# circuito_rele.net
KiCad netlist of a schematic drawn in EAGLE
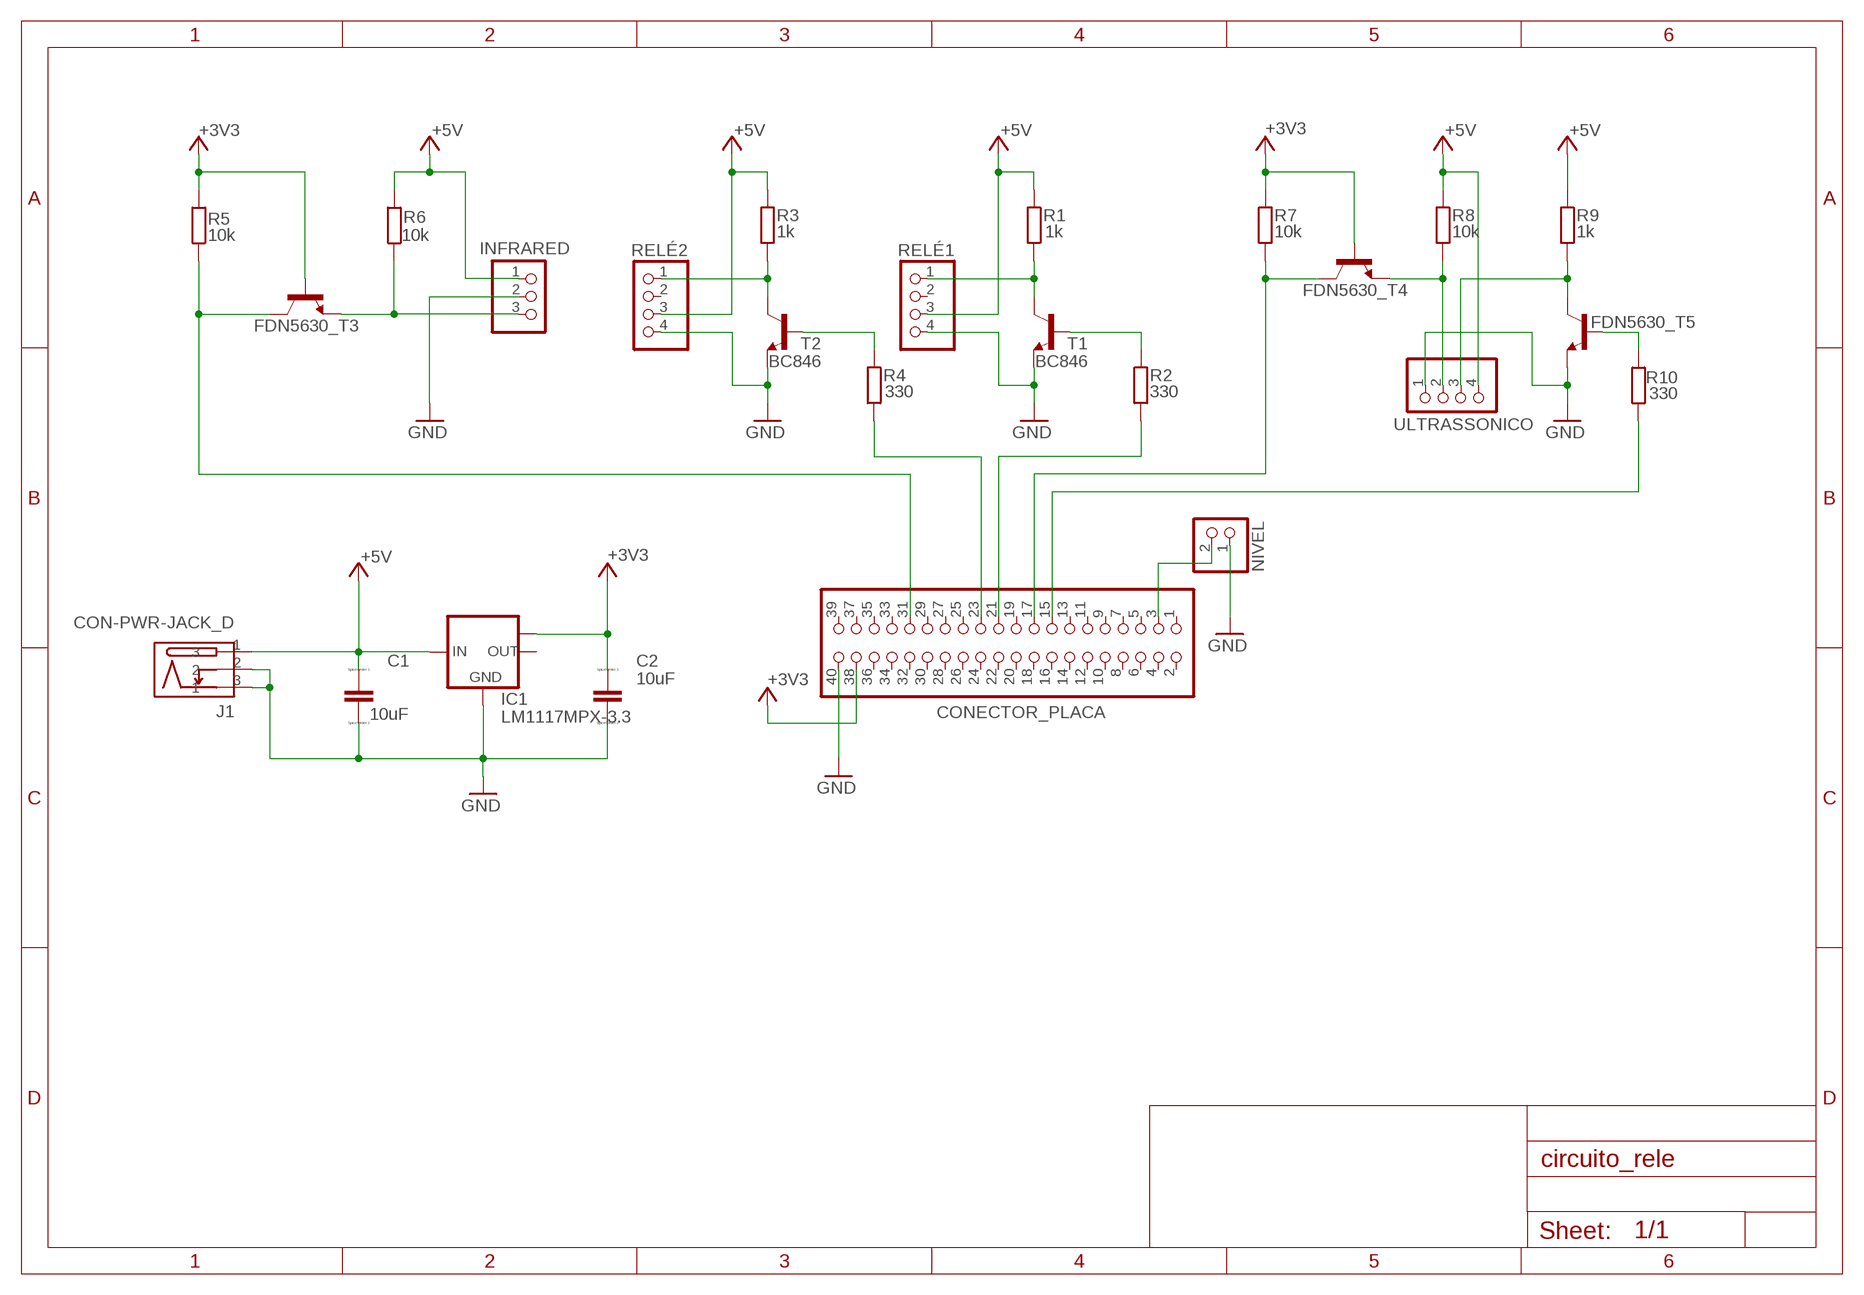
[diagram p0: schematic, sheet 1]

(export (version "E")
  (design (tool "Eeschema 10.0.6"))
  (components
    (comp (ref "C1")
      (value "10uF")
      (footprint "eagle-import:C4532")
      (libsource (lib "eagle-import") (part "CC4532"))
    )
    (comp (ref "C2")
      (value "10uF")
      (footprint "eagle-import:C4532")
      (libsource (lib "eagle-import") (part "CC4532"))
    )
    (comp (ref "CONECTOR_PLACA")
      (value "PINHD-2X20")
      (footprint "eagle-import:2X20")
      (libsource (lib "eagle-import") (part "PINHD-2X20"))
    )
    (comp (ref "FDN5630_T3")
      (value "BC846")
      (footprint "eagle-import:SOT23")
      (libsource (lib "eagle-import") (part "BC846"))
    )
    (comp (ref "FDN5630_T4")
      (value "BC846")
      (footprint "eagle-import:SOT23")
      (libsource (lib "eagle-import") (part "BC846"))
    )
    (comp (ref "FDN5630_T5")
      (value "BC846")
      (footprint "eagle-import:SOT23")
      (libsource (lib "eagle-import") (part "BC846"))
    )
    (comp (ref "IC1")
      (value "LM1117MPX-3.3")
      (footprint "eagle-import:SOT223")
      (libsource (lib "eagle-import") (part "LM1117MPX-3.3"))
    )
    (comp (ref "INFRARED")
      (value "PINHD-1X3")
      (footprint "eagle-import:1X03")
      (libsource (lib "eagle-import") (part "PINHD-1X3"))
    )
    (comp (ref "J1")
      (value "CON-PWR-JACK_D")
      (footprint "eagle-import:TDC-002-3")
      (libsource (lib "eagle-import") (part "CON-PWR-JACK_D"))
    )
    (comp (ref "NIVEL")
      (value "PINHD-1X2")
      (footprint "eagle-import:1X02")
      (libsource (lib "eagle-import") (part "PINHD-1X2"))
    )
    (comp (ref "R1")
      (value "1k")
      (footprint "eagle-import:0207_10")
      (libsource (lib "eagle-import") (part "R-EU_0207/10"))
    )
    (comp (ref "R2")
      (value "330")
      (footprint "eagle-import:0207_10")
      (libsource (lib "eagle-import") (part "R-EU_0207/10"))
    )
    (comp (ref "R3")
      (value "1k")
      (footprint "eagle-import:0207_10")
      (libsource (lib "eagle-import") (part "R-EU_0207/10"))
    )
    (comp (ref "R4")
      (value "330")
      (footprint "eagle-import:0207_10")
      (libsource (lib "eagle-import") (part "R-EU_0207/10"))
    )
    (comp (ref "R5")
      (value "10k")
      (footprint "eagle-import:0207_10")
      (libsource (lib "eagle-import") (part "R-EU_0207/10"))
    )
    (comp (ref "R6")
      (value "10k")
      (footprint "eagle-import:0207_10")
      (libsource (lib "eagle-import") (part "R-EU_0207/10"))
    )
    (comp (ref "R7")
      (value "10k")
      (footprint "eagle-import:0207_10")
      (libsource (lib "eagle-import") (part "R-EU_0207/10"))
    )
    (comp (ref "R8")
      (value "10k")
      (footprint "eagle-import:0207_10")
      (libsource (lib "eagle-import") (part "R-EU_0207/10"))
    )
    (comp (ref "R9")
      (value "1k")
      (footprint "eagle-import:0207_10")
      (libsource (lib "eagle-import") (part "R-EU_0207/10"))
    )
    (comp (ref "R10")
      (value "330")
      (footprint "eagle-import:0207_10")
      (libsource (lib "eagle-import") (part "R-EU_0207/10"))
    )
    (comp (ref "RELÉ1")
      (value "PINHD-1X4")
      (footprint "eagle-import:1X04")
      (libsource (lib "eagle-import") (part "PINHD-1X4"))
    )
    (comp (ref "RELÉ2")
      (value "PINHD-1X4")
      (footprint "eagle-import:1X04")
      (libsource (lib "eagle-import") (part "PINHD-1X4"))
    )
    (comp (ref "T1")
      (value "BC846")
      (footprint "eagle-import:SOT23")
      (libsource (lib "eagle-import") (part "BC846"))
    )
    (comp (ref "T2")
      (value "BC846")
      (footprint "eagle-import:SOT23")
      (libsource (lib "eagle-import") (part "BC846"))
    )
    (comp (ref "ULTRASSONICO")
      (value "PINHD-1X4")
      (footprint "eagle-import:1X04")
      (libsource (lib "eagle-import") (part "PINHD-1X4"))
    )
  )
  (nets
    (net (code "1") (name "+3V3") (class "Default")
      (node (ref "C2") (pin "1") (pinfunction "1_1") (pintype "passive"))
      (node (ref "CONECTOR_PLACA") (pin "38") (pinfunction "38_38") (pintype "passive"))
      (node (ref "FDN5630_T3") (pin "1") (pinfunction "B_1") (pintype "passive"))
      (node (ref "FDN5630_T4") (pin "1") (pinfunction "B_1") (pintype "passive"))
      (node (ref "IC1") (pin "TAB") (pinfunction "OUT1_TAB") (pintype "passive"))
      (node (ref "R5") (pin "2") (pinfunction "2_2") (pintype "passive"))
      (node (ref "R7") (pin "1") (pinfunction "1_1") (pintype "passive"))
    )
    (net (code "2") (name "+5V") (class "Default")
      (node (ref "C1") (pin "1") (pinfunction "1_1") (pintype "passive"))
      (node (ref "IC1") (pin "3") (pinfunction "IN_3") (pintype "input"))
      (node (ref "INFRARED") (pin "1") (pinfunction "1_1") (pintype "passive"))
      (node (ref "J1") (pin "1") (pinfunction "3_1") (pintype "passive"))
      (node (ref "R1") (pin "1") (pinfunction "1_1") (pintype "passive"))
      (node (ref "R3") (pin "1") (pinfunction "1_1") (pintype "passive"))
      (node (ref "R6") (pin "2") (pinfunction "2_2") (pintype "passive"))
      (node (ref "R8") (pin "1") (pinfunction "1_1") (pintype "passive"))
      (node (ref "R9") (pin "1") (pinfunction "1_1") (pintype "passive"))
      (node (ref "RELÉ1") (pin "3") (pinfunction "3_3") (pintype "passive"))
      (node (ref "RELÉ2") (pin "3") (pinfunction "3_3") (pintype "passive"))
      (node (ref "ULTRASSONICO") (pin "4") (pinfunction "4_4") (pintype "passive"))
    )
    (net (code "3") (name "GND") (class "Default")
      (node (ref "C1") (pin "2") (pinfunction "2_2") (pintype "passive"))
      (node (ref "C2") (pin "2") (pinfunction "2_2") (pintype "passive"))
      (node (ref "CONECTOR_PLACA") (pin "40") (pinfunction "40_40") (pintype "passive"))
      (node (ref "FDN5630_T5") (pin "2") (pinfunction "E_2") (pintype "passive"))
      (node (ref "IC1") (pin "1") (pinfunction "GND_1") (pintype "input"))
      (node (ref "INFRARED") (pin "2") (pinfunction "2_2") (pintype "passive"))
      (node (ref "J1") (pin "2") (pinfunction "2_2") (pintype "passive"))
      (node (ref "J1") (pin "3") (pinfunction "1_3") (pintype "passive"))
      (node (ref "NIVEL") (pin "1") (pinfunction "1_1") (pintype "passive"))
      (node (ref "RELÉ1") (pin "4") (pinfunction "4_4") (pintype "passive"))
      (node (ref "RELÉ2") (pin "4") (pinfunction "4_4") (pintype "passive"))
      (node (ref "T1") (pin "2") (pinfunction "E_2") (pintype "passive"))
      (node (ref "T2") (pin "2") (pinfunction "E_2") (pintype "passive"))
      (node (ref "ULTRASSONICO") (pin "1") (pinfunction "1_1") (pintype "passive"))
    )
    (net (code "4") (name "Net-(CONECTOR_PLACA-Pad3)") (class "Default")
      (node (ref "CONECTOR_PLACA") (pin "3") (pinfunction "3_3") (pintype "passive"))
      (node (ref "NIVEL") (pin "2") (pinfunction "2_2") (pintype "passive"))
    )
    (net (code "5") (name "Net-(CONECTOR_PLACA-Pad15)") (class "Default")
      (node (ref "CONECTOR_PLACA") (pin "15") (pinfunction "15_15") (pintype "passive"))
      (node (ref "R10") (pin "1") (pinfunction "1_1") (pintype "passive"))
    )
    (net (code "6") (name "Net-(CONECTOR_PLACA-Pad21)") (class "Default")
      (node (ref "CONECTOR_PLACA") (pin "21") (pinfunction "21_21") (pintype "passive"))
      (node (ref "R2") (pin "2") (pinfunction "2_2") (pintype "passive"))
    )
    (net (code "7") (name "Net-(CONECTOR_PLACA-Pad23)") (class "Default")
      (node (ref "CONECTOR_PLACA") (pin "23") (pinfunction "23_23") (pintype "passive"))
      (node (ref "R4") (pin "2") (pinfunction "2_2") (pintype "passive"))
    )
    (net (code "8") (name "Net-(FDN5630_T3-C)") (class "Default")
      (node (ref "CONECTOR_PLACA") (pin "31") (pinfunction "31_31") (pintype "passive"))
      (node (ref "FDN5630_T3") (pin "3") (pinfunction "C_3") (pintype "passive"))
      (node (ref "R5") (pin "1") (pinfunction "1_1") (pintype "passive"))
    )
    (net (code "9") (name "Net-(FDN5630_T3-E)") (class "Default")
      (node (ref "FDN5630_T3") (pin "2") (pinfunction "E_2") (pintype "passive"))
      (node (ref "INFRARED") (pin "3") (pinfunction "3_3") (pintype "passive"))
      (node (ref "R6") (pin "1") (pinfunction "1_1") (pintype "passive"))
    )
    (net (code "10") (name "Net-(FDN5630_T4-C)") (class "Default")
      (node (ref "CONECTOR_PLACA") (pin "17") (pinfunction "17_17") (pintype "passive"))
      (node (ref "FDN5630_T4") (pin "3") (pinfunction "C_3") (pintype "passive"))
      (node (ref "R7") (pin "2") (pinfunction "2_2") (pintype "passive"))
    )
    (net (code "11") (name "Net-(FDN5630_T4-E)") (class "Default")
      (node (ref "FDN5630_T4") (pin "2") (pinfunction "E_2") (pintype "passive"))
      (node (ref "R8") (pin "2") (pinfunction "2_2") (pintype "passive"))
      (node (ref "ULTRASSONICO") (pin "2") (pinfunction "2_2") (pintype "passive"))
    )
    (net (code "12") (name "Net-(FDN5630_T5-B)") (class "Default")
      (node (ref "FDN5630_T5") (pin "1") (pinfunction "B_1") (pintype "passive"))
      (node (ref "R10") (pin "2") (pinfunction "2_2") (pintype "passive"))
    )
    (net (code "13") (name "Net-(FDN5630_T5-C)") (class "Default")
      (node (ref "FDN5630_T5") (pin "3") (pinfunction "C_3") (pintype "passive"))
      (node (ref "R9") (pin "2") (pinfunction "2_2") (pintype "passive"))
      (node (ref "ULTRASSONICO") (pin "3") (pinfunction "3_3") (pintype "passive"))
    )
    (net (code "14") (name "Net-(T1-B)") (class "Default")
      (node (ref "R2") (pin "1") (pinfunction "1_1") (pintype "passive"))
      (node (ref "T1") (pin "1") (pinfunction "B_1") (pintype "passive"))
    )
    (net (code "15") (name "Net-(T1-C)") (class "Default")
      (node (ref "R1") (pin "2") (pinfunction "2_2") (pintype "passive"))
      (node (ref "RELÉ1") (pin "1") (pinfunction "1_1") (pintype "passive"))
      (node (ref "T1") (pin "3") (pinfunction "C_3") (pintype "passive"))
    )
    (net (code "16") (name "Net-(T2-B)") (class "Default")
      (node (ref "R4") (pin "1") (pinfunction "1_1") (pintype "passive"))
      (node (ref "T2") (pin "1") (pinfunction "B_1") (pintype "passive"))
    )
    (net (code "17") (name "Net-(T2-C)") (class "Default")
      (node (ref "R3") (pin "2") (pinfunction "2_2") (pintype "passive"))
      (node (ref "RELÉ2") (pin "1") (pinfunction "1_1") (pintype "passive"))
      (node (ref "T2") (pin "3") (pinfunction "C_3") (pintype "passive"))
    )
    (net (code "18") (name "unconnected-(CONECTOR_PLACA-Pad1)") (class "Default")
      (node (ref "CONECTOR_PLACA") (pin "1") (pinfunction "1_1") (pintype "passive"))
    )
    (net (code "19") (name "unconnected-(CONECTOR_PLACA-Pad2)") (class "Default")
      (node (ref "CONECTOR_PLACA") (pin "2") (pinfunction "2_2") (pintype "passive"))
    )
    (net (code "20") (name "unconnected-(CONECTOR_PLACA-Pad4)") (class "Default")
      (node (ref "CONECTOR_PLACA") (pin "4") (pinfunction "4_4") (pintype "passive"))
    )
    (net (code "21") (name "unconnected-(CONECTOR_PLACA-Pad5)") (class "Default")
      (node (ref "CONECTOR_PLACA") (pin "5") (pinfunction "5_5") (pintype "passive"))
    )
    (net (code "22") (name "unconnected-(CONECTOR_PLACA-Pad6)") (class "Default")
      (node (ref "CONECTOR_PLACA") (pin "6") (pinfunction "6_6") (pintype "passive"))
    )
    (net (code "23") (name "unconnected-(CONECTOR_PLACA-Pad7)") (class "Default")
      (node (ref "CONECTOR_PLACA") (pin "7") (pinfunction "7_7") (pintype "passive"))
    )
    (net (code "24") (name "unconnected-(CONECTOR_PLACA-Pad8)") (class "Default")
      (node (ref "CONECTOR_PLACA") (pin "8") (pinfunction "8_8") (pintype "passive"))
    )
    (net (code "25") (name "unconnected-(CONECTOR_PLACA-Pad9)") (class "Default")
      (node (ref "CONECTOR_PLACA") (pin "9") (pinfunction "9_9") (pintype "passive"))
    )
    (net (code "26") (name "unconnected-(CONECTOR_PLACA-Pad10)") (class "Default")
      (node (ref "CONECTOR_PLACA") (pin "10") (pinfunction "10_10") (pintype "passive"))
    )
    (net (code "27") (name "unconnected-(CONECTOR_PLACA-Pad11)") (class "Default")
      (node (ref "CONECTOR_PLACA") (pin "11") (pinfunction "11_11") (pintype "passive"))
    )
    (net (code "28") (name "unconnected-(CONECTOR_PLACA-Pad12)") (class "Default")
      (node (ref "CONECTOR_PLACA") (pin "12") (pinfunction "12_12") (pintype "passive"))
    )
    (net (code "29") (name "unconnected-(CONECTOR_PLACA-Pad13)") (class "Default")
      (node (ref "CONECTOR_PLACA") (pin "13") (pinfunction "13_13") (pintype "passive"))
    )
    (net (code "30") (name "unconnected-(CONECTOR_PLACA-Pad14)") (class "Default")
      (node (ref "CONECTOR_PLACA") (pin "14") (pinfunction "14_14") (pintype "passive"))
    )
    (net (code "31") (name "unconnected-(CONECTOR_PLACA-Pad16)") (class "Default")
      (node (ref "CONECTOR_PLACA") (pin "16") (pinfunction "16_16") (pintype "passive"))
    )
    (net (code "32") (name "unconnected-(CONECTOR_PLACA-Pad18)") (class "Default")
      (node (ref "CONECTOR_PLACA") (pin "18") (pinfunction "18_18") (pintype "passive"))
    )
    (net (code "33") (name "unconnected-(CONECTOR_PLACA-Pad19)") (class "Default")
      (node (ref "CONECTOR_PLACA") (pin "19") (pinfunction "19_19") (pintype "passive"))
    )
    (net (code "34") (name "unconnected-(CONECTOR_PLACA-Pad20)") (class "Default")
      (node (ref "CONECTOR_PLACA") (pin "20") (pinfunction "20_20") (pintype "passive"))
    )
    (net (code "35") (name "unconnected-(CONECTOR_PLACA-Pad22)") (class "Default")
      (node (ref "CONECTOR_PLACA") (pin "22") (pinfunction "22_22") (pintype "passive"))
    )
    (net (code "36") (name "unconnected-(CONECTOR_PLACA-Pad24)") (class "Default")
      (node (ref "CONECTOR_PLACA") (pin "24") (pinfunction "24_24") (pintype "passive"))
    )
    (net (code "37") (name "unconnected-(CONECTOR_PLACA-Pad25)") (class "Default")
      (node (ref "CONECTOR_PLACA") (pin "25") (pinfunction "25_25") (pintype "passive"))
    )
    (net (code "38") (name "unconnected-(CONECTOR_PLACA-Pad26)") (class "Default")
      (node (ref "CONECTOR_PLACA") (pin "26") (pinfunction "26_26") (pintype "passive"))
    )
    (net (code "39") (name "unconnected-(CONECTOR_PLACA-Pad27)") (class "Default")
      (node (ref "CONECTOR_PLACA") (pin "27") (pinfunction "27_27") (pintype "passive"))
    )
    (net (code "40") (name "unconnected-(CONECTOR_PLACA-Pad28)") (class "Default")
      (node (ref "CONECTOR_PLACA") (pin "28") (pinfunction "28_28") (pintype "passive"))
    )
    (net (code "41") (name "unconnected-(CONECTOR_PLACA-Pad29)") (class "Default")
      (node (ref "CONECTOR_PLACA") (pin "29") (pinfunction "29_29") (pintype "passive"))
    )
    (net (code "42") (name "unconnected-(CONECTOR_PLACA-Pad30)") (class "Default")
      (node (ref "CONECTOR_PLACA") (pin "30") (pinfunction "30_30") (pintype "passive"))
    )
    (net (code "43") (name "unconnected-(CONECTOR_PLACA-Pad32)") (class "Default")
      (node (ref "CONECTOR_PLACA") (pin "32") (pinfunction "32_32") (pintype "passive"))
    )
    (net (code "44") (name "unconnected-(CONECTOR_PLACA-Pad33)") (class "Default")
      (node (ref "CONECTOR_PLACA") (pin "33") (pinfunction "33_33") (pintype "passive"))
    )
    (net (code "45") (name "unconnected-(CONECTOR_PLACA-Pad34)") (class "Default")
      (node (ref "CONECTOR_PLACA") (pin "34") (pinfunction "34_34") (pintype "passive"))
    )
    (net (code "46") (name "unconnected-(CONECTOR_PLACA-Pad35)") (class "Default")
      (node (ref "CONECTOR_PLACA") (pin "35") (pinfunction "35_35") (pintype "passive"))
    )
    (net (code "47") (name "unconnected-(CONECTOR_PLACA-Pad36)") (class "Default")
      (node (ref "CONECTOR_PLACA") (pin "36") (pinfunction "36_36") (pintype "passive"))
    )
    (net (code "48") (name "unconnected-(CONECTOR_PLACA-Pad37)") (class "Default")
      (node (ref "CONECTOR_PLACA") (pin "37") (pinfunction "37_37") (pintype "passive"))
    )
    (net (code "49") (name "unconnected-(CONECTOR_PLACA-Pad39)") (class "Default")
      (node (ref "CONECTOR_PLACA") (pin "39") (pinfunction "39_39") (pintype "passive"))
    )
    (net (code "50") (name "unconnected-(IC1-OUT-Pad2)") (class "Default")
      (node (ref "IC1") (pin "2") (pinfunction "OUT_2") (pintype "passive"))
    )
    (net (code "51") (name "unconnected-(RELÉ1-Pad2)") (class "Default")
      (node (ref "RELÉ1") (pin "2") (pinfunction "2_2") (pintype "passive"))
    )
    (net (code "52") (name "unconnected-(RELÉ2-Pad2)") (class "Default")
      (node (ref "RELÉ2") (pin "2") (pinfunction "2_2") (pintype "passive"))
    )
  )
)
